# USBINFRTransiever_USBUART.net
KiCad netlist of a schematic drawn in Altium Designer
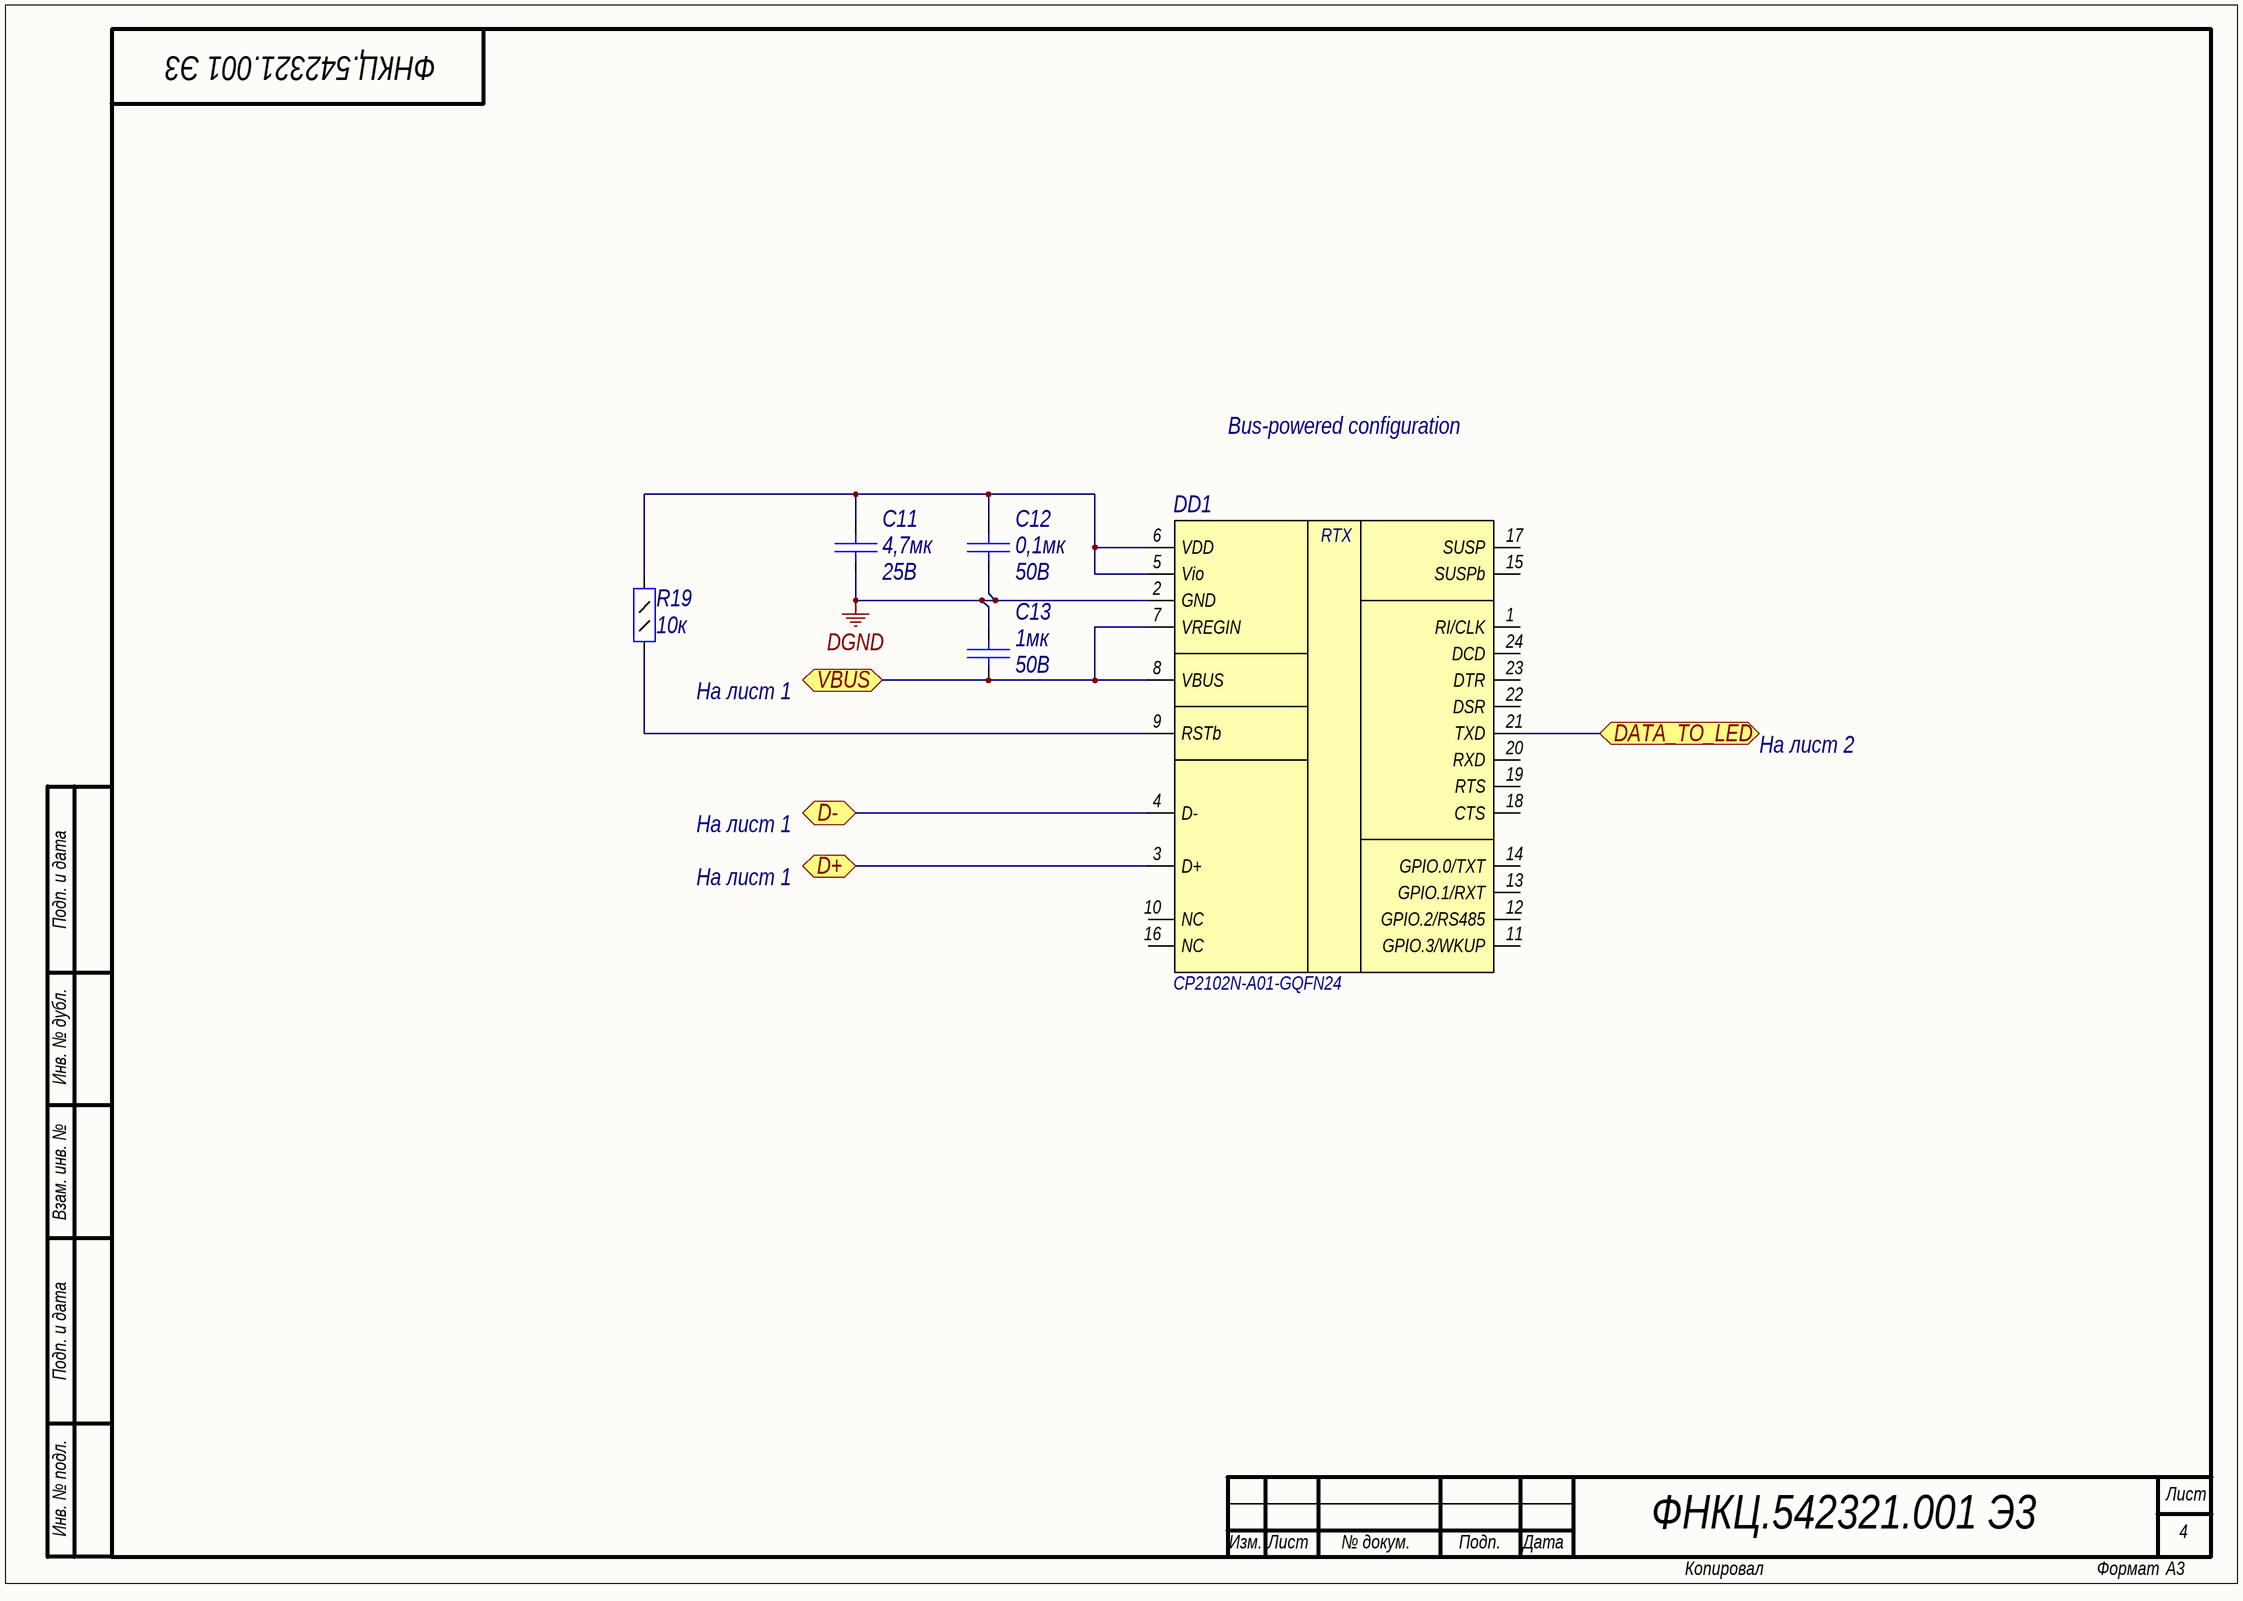
[diagram p0: USBINFRTransiever_USBUART.SchDoc]

(export (version "E")
  (design (tool "Eeschema 10.0.6"))
  (components
    (comp (ref "C11")
      (value "4,7мк")
      (footprint "C0805")
      (description "Конденсатор")
      (fields
        (field (name "VOLTAGE") "25B")
        (field (name "PART NUMBER") "GRM21BR61E475KA12L")
        (field (name "Comment") "Capacitor")
      )
      (libsource (lib "MOP44") (part "Capacitor"))
    )
    (comp (ref "C12")
      (value "0,1мк")
      (footprint "C0805")
      (description "Конденсатор")
      (fields
        (field (name "VOLTAGE") "50B")
        (field (name "PART NUMBER") "GRM21BR71H104K**")
        (field (name "Comment") "Capacitor")
      )
      (libsource (lib "MOP44") (part "Capacitor"))
    )
    (comp (ref "C13")
      (value "1мк")
      (footprint "C0805")
      (description "Конденсатор")
      (fields
        (field (name "VOLTAGE") "50B")
        (field (name "PART NUMBER") "GRM21BR71H105K")
        (field (name "Comment") "Capacitor")
      )
      (libsource (lib "MOP44") (part "Capacitor"))
    )
    (comp (ref "DD1")
      (value "CP2102N-A01-GQFN24")
      (footprint "QFN24")
      (description "USB-UART преобразователь")
      (libsource (lib "MOP44") (part "CP2102N-A01-GQFN24"))
    )
    (comp (ref "R19")
      (value "10к")
      (footprint "R0805")
      (description "Резистор")
      (fields (field (name "PART NUMBER") "RC0805FR-0710KL") (field (name "POWER") "0,125Вт"))
      (libsource (lib "MOP44") (part "Resistor_0,125Вт"))
    )
  )
  (nets
    (net (code "1") (name "/D+") (class "Default")
      (node (ref "DD1") (pin "3") (pinfunction "D+_3") (pintype "passive"))
    )
    (net (code "2") (name "/D-") (class "Default")
      (node (ref "DD1") (pin "4") (pinfunction "D-_4") (pintype "passive"))
    )
    (net (code "3") (name "/DATA_TO_LED") (class "Default")
      (node (ref "DD1") (pin "21") (pinfunction "TXD_21") (pintype "passive"))
    )
    (net (code "4") (name "/VBUS") (class "Default")
      (node (ref "C13") (pin "1") (pinfunction "1_1") (pintype "passive"))
      (node (ref "DD1") (pin "7") (pinfunction "VREGIN_7") (pintype "passive"))
      (node (ref "DD1") (pin "8") (pinfunction "VBUS_8") (pintype "passive"))
    )
    (net (code "5") (name "DGND") (class "Default")
      (node (ref "C11") (pin "1") (pinfunction "1_1") (pintype "passive"))
      (node (ref "C12") (pin "1") (pinfunction "1_1") (pintype "passive"))
      (node (ref "C13") (pin "2") (pinfunction "2_2") (pintype "passive"))
      (node (ref "DD1") (pin "2") (pinfunction "GND_2") (pintype "passive"))
    )
    (net (code "6") (name "Net-(DD1-RSTb)") (class "Default")
      (node (ref "DD1") (pin "9") (pinfunction "RSTb_9") (pintype "passive"))
      (node (ref "R19") (pin "1") (pinfunction "1_1") (pintype "passive"))
    )
    (net (code "7") (name "Net-(DD1-VDD)") (class "Default")
      (node (ref "C11") (pin "2") (pinfunction "2_2") (pintype "passive"))
      (node (ref "C12") (pin "2") (pinfunction "2_2") (pintype "passive"))
      (node (ref "DD1") (pin "5") (pinfunction "Vio_5") (pintype "passive"))
      (node (ref "DD1") (pin "6") (pinfunction "VDD_6") (pintype "passive"))
      (node (ref "R19") (pin "2") (pinfunction "2_2") (pintype "passive"))
    )
    (net (code "8") (name "unconnected-(DD1-CTS-Pad18)") (class "Default")
      (node (ref "DD1") (pin "18") (pinfunction "CTS_18") (pintype "passive"))
    )
    (net (code "9") (name "unconnected-(DD1-DCD-Pad24)") (class "Default")
      (node (ref "DD1") (pin "24") (pinfunction "DCD_24") (pintype "passive"))
    )
    (net (code "10") (name "unconnected-(DD1-DSR-Pad22)") (class "Default")
      (node (ref "DD1") (pin "22") (pinfunction "DSR_22") (pintype "passive"))
    )
    (net (code "11") (name "unconnected-(DD1-DTR-Pad23)") (class "Default")
      (node (ref "DD1") (pin "23") (pinfunction "DTR_23") (pintype "passive"))
    )
    (net (code "12") (name "unconnected-(DD1-GPIO.0{slash}TXT-Pad14)") (class "Default")
      (node (ref "DD1") (pin "14") (pinfunction "GPIO.0/TXT_14") (pintype "passive"))
    )
    (net (code "13") (name "unconnected-(DD1-GPIO.1{slash}RXT-Pad13)") (class "Default")
      (node (ref "DD1") (pin "13") (pinfunction "GPIO.1/RXT_13") (pintype "passive"))
    )
    (net (code "14") (name "unconnected-(DD1-GPIO.2{slash}RS485-Pad12)") (class "Default")
      (node (ref "DD1") (pin "12") (pinfunction "GPIO.2/RS485_12") (pintype "passive"))
    )
    (net (code "15") (name "unconnected-(DD1-GPIO.3{slash}WKUP-Pad11)") (class "Default")
      (node (ref "DD1") (pin "11") (pinfunction "GPIO.3/WKUP_11") (pintype "passive"))
    )
    (net (code "16") (name "unconnected-(DD1-NC-Pad10)") (class "Default")
      (node (ref "DD1") (pin "10") (pinfunction "NC_10") (pintype "passive"))
    )
    (net (code "17") (name "unconnected-(DD1-NC-Pad16)") (class "Default")
      (node (ref "DD1") (pin "16") (pinfunction "NC_16") (pintype "passive"))
    )
    (net (code "18") (name "unconnected-(DD1-RI{slash}CLK-Pad1)") (class "Default")
      (node (ref "DD1") (pin "1") (pinfunction "RI/CLK_1") (pintype "passive"))
    )
    (net (code "19") (name "unconnected-(DD1-RTS-Pad19)") (class "Default")
      (node (ref "DD1") (pin "19") (pinfunction "RTS_19") (pintype "passive"))
    )
    (net (code "20") (name "unconnected-(DD1-RXD-Pad20)") (class "Default")
      (node (ref "DD1") (pin "20") (pinfunction "RXD_20") (pintype "passive"))
    )
    (net (code "21") (name "unconnected-(DD1-SUSP-Pad17)") (class "Default")
      (node (ref "DD1") (pin "17") (pinfunction "SUSP_17") (pintype "passive"))
    )
    (net (code "22") (name "unconnected-(DD1-SUSPb-Pad15)") (class "Default")
      (node (ref "DD1") (pin "15") (pinfunction "SUSPb_15") (pintype "passive"))
    )
  )
)
